# DSO_Power.net
KiCad netlist of a schematic drawn in Altium Designer
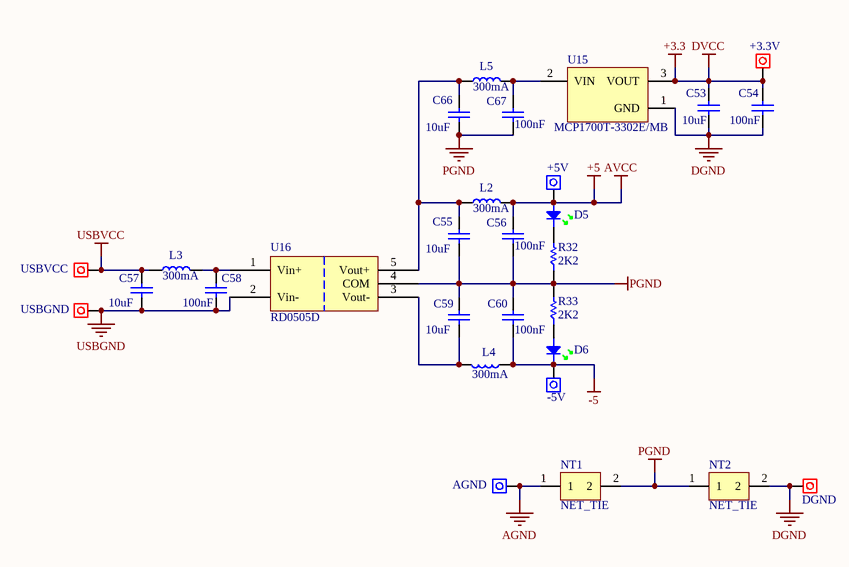
[diagram p0: DSO_Power.SchDoc]

(export (version "E")
  (design (tool "Eeschema 10.0.6"))
  (components
    (comp (ref "C53")
      (value "10uF")
      (footprint "0805C")
      (description "Capacitor")
      (fields (field (name "REVIEWED BY") "RM - 2018/08/05"))
      (libsource (lib "DSO") (part "C"))
    )
    (comp (ref "C54")
      (value "100nF")
      (footprint "0805C")
      (description "Capacitor")
      (fields (field (name "REVIEWED BY") "RM - 2018/08/05"))
      (libsource (lib "DSO") (part "C"))
    )
    (comp (ref "C55")
      (value "10uF")
      (footprint "0805C")
      (description "Capacitor")
      (fields (field (name "REVIEWED BY") "RM - 2018/08/05"))
      (libsource (lib "DSO") (part "C"))
    )
    (comp (ref "C56")
      (value "100nF")
      (footprint "0805C")
      (description "Capacitor")
      (fields (field (name "REVIEWED BY") "RM - 2018/08/05"))
      (libsource (lib "DSO") (part "C"))
    )
    (comp (ref "C57")
      (value "10uF")
      (footprint "0805C")
      (description "Capacitor")
      (fields (field (name "REVIEWED BY") "RM - 2018/08/05"))
      (libsource (lib "DSO") (part "C"))
    )
    (comp (ref "C58")
      (value "100nF")
      (footprint "0805C")
      (description "Capacitor")
      (fields (field (name "REVIEWED BY") "RM - 2018/08/05"))
      (libsource (lib "DSO") (part "C"))
    )
    (comp (ref "C59")
      (value "10uF")
      (footprint "0805C")
      (description "Capacitor")
      (fields (field (name "REVIEWED BY") "RM - 2018/08/05"))
      (libsource (lib "DSO") (part "C"))
    )
    (comp (ref "C60")
      (value "100nF")
      (footprint "0805C")
      (description "Capacitor")
      (fields (field (name "REVIEWED BY") "RM - 2018/08/05"))
      (libsource (lib "DSO") (part "C"))
    )
    (comp (ref "C66")
      (value "10uF")
      (footprint "0805C")
      (description "Capacitor")
      (fields (field (name "REVIEWED BY") "RM - 2018/08/05"))
      (libsource (lib "DSO") (part "C"))
    )
    (comp (ref "C67")
      (value "100nF")
      (footprint "0805C")
      (description "Capacitor")
      (fields (field (name "REVIEWED BY") "RM - 2018/08/05"))
      (libsource (lib "DSO") (part "C"))
    )
    (comp (ref "D5")
      (value "+5V")
      (footprint "0805D-GREEN")
      (description "Light Emitting Diode")
      (fields (field (name "REVIEWED BY") "RM - 2018/08/05"))
      (libsource (lib "DSO") (part "LED GREEN"))
    )
    (comp (ref "D6")
      (value "-5V")
      (footprint "0805D-GREEN")
      (description "Light Emitting Diode")
      (fields (field (name "REVIEWED BY") "RM - 2018/08/05"))
      (libsource (lib "DSO") (part "LED GREEN"))
    )
    (comp (ref "L2")
      (value "300mA")
      (footprint "0805")
      (description "Inductor")
      (fields (field (name "REVIEWED BY") "RM - 2018/08/05"))
      (libsource (lib "DSO") (part "I"))
    )
    (comp (ref "L3")
      (value "300mA")
      (footprint "0805")
      (description "Inductor")
      (fields (field (name "REVIEWED BY") "RM - 2018/08/05"))
      (libsource (lib "DSO") (part "I"))
    )
    (comp (ref "L4")
      (value "300mA")
      (footprint "0805")
      (description "Inductor")
      (fields (field (name "REVIEWED BY") "RM - 2018/08/05"))
      (libsource (lib "DSO") (part "I"))
    )
    (comp (ref "L5")
      (value "300mA")
      (footprint "0805")
      (description "Inductor")
      (fields (field (name "REVIEWED BY") "RM - 2018/08/05"))
      (libsource (lib "DSO") (part "I"))
    )
    (comp (ref "NT1")
      (value "NET_TIE")
      (footprint "NET_TIE")
      (description "Net Tie")
      (libsource (lib "DSO") (part "NET_TIE"))
    )
    (comp (ref "NT2")
      (value "NET_TIE")
      (footprint "NET_TIE")
      (description "Net Tie")
      (libsource (lib "DSO") (part "NET_TIE"))
    )
    (comp (ref "R32")
      (value "2K2")
      (footprint "0805")
      (description "Resistor")
      (fields (field (name "REVIEWED BY") "RM - 2018/08/05"))
      (libsource (lib "DSO") (part "R"))
    )
    (comp (ref "R33")
      (value "2K2")
      (footprint "0805")
      (description "Resistor")
      (fields (field (name "REVIEWED BY") "RM - 2018/08/05"))
      (libsource (lib "DSO") (part "R"))
    )
    (comp (ref "TP4")
      (value "+3.3V")
      (footprint "Testpoin")
      (description "Pad")
      (libsource (lib "DSO") (part "Test Point"))
    )
    (comp (ref "TP5")
      (value "DGND")
      (footprint "Testpoin")
      (description "Pad")
      (libsource (lib "DSO") (part "Test Point"))
    )
    (comp (ref "TP6")
      (value "+5V")
      (footprint "PIN 1.8mm")
      (description "Pad")
      (libsource (lib "DSO") (part "WIRE"))
    )
    (comp (ref "TP8")
      (value "USBVCC")
      (footprint "Testpoin")
      (description "Pad")
      (libsource (lib "DSO") (part "Test Point"))
    )
    (comp (ref "TP9")
      (value "USBGND")
      (footprint "Testpoin")
      (description "Pad")
      (libsource (lib "DSO") (part "Test Point"))
    )
    (comp (ref "TP10")
      (value "-5V")
      (footprint "PIN 1.8mm")
      (description "Pad")
      (libsource (lib "DSO") (part "WIRE"))
    )
    (comp (ref "TP11")
      (value "AGND")
      (footprint "PIN 1.8mm")
      (description "Pad")
      (libsource (lib "DSO") (part "WIRE"))
    )
    (comp (ref "U15")
      (value "MCP1700T-3302E/MB")
      (footprint "SOT89")
      (description "Low Quiescent Current LDO, 3-Pin SOT-89, Extended Temperature, Tape and Reel")
      (fields (field (name "REVIEWED BY") "RM - 2018/08/05"))
      (libsource (lib "DSO") (part "MCP1700T"))
    )
    (comp (ref "U16")
      (value "RD0505D")
      (footprint "SIP_NMG")
      (description "(ADV) DC to DC converter 5V in +-5V out")
      (fields (field (name "REVIEWED BY") "RM - 2018/08/05"))
      (libsource (lib "DSO") (part "RD0505D"))
    )
  )
  (nets
    (net (code "1") (name "+3.3") (class "Default")
      (node (ref "C53") (pin "1") (pinfunction "1_1") (pintype "passive"))
      (node (ref "C54") (pin "1") (pinfunction "1_1") (pintype "passive"))
      (node (ref "TP4") (pin "1") (pintype "passive"))
      (node (ref "U15") (pin "3") (pinfunction "VOUT_3") (pintype "power_in"))
    )
    (net (code "2") (name "+5") (class "Default")
      (node (ref "C56") (pin "1") (pinfunction "1_1") (pintype "passive"))
      (node (ref "D5") (pin "A") (pinfunction "A_A") (pintype "passive"))
      (node (ref "L2") (pin "2") (pinfunction "2_2") (pintype "passive"))
      (node (ref "TP6") (pin "1") (pintype "passive"))
    )
    (net (code "3") (name "-5") (class "Default")
      (node (ref "C60") (pin "1") (pinfunction "1_1") (pintype "passive"))
      (node (ref "D6") (pin "K") (pinfunction "K_K") (pintype "passive"))
      (node (ref "L4") (pin "1") (pinfunction "1_1") (pintype "passive"))
      (node (ref "TP10") (pin "1") (pintype "passive"))
    )
    (net (code "4") (name "AGND") (class "Default")
      (node (ref "NT1") (pin "1") (pinfunction "1_1") (pintype "passive"))
      (node (ref "TP11") (pin "1") (pintype "passive"))
    )
    (net (code "5") (name "DGND") (class "Default")
      (node (ref "C53") (pin "2") (pinfunction "2_2") (pintype "passive"))
      (node (ref "C54") (pin "2") (pinfunction "2_2") (pintype "passive"))
      (node (ref "NT2") (pin "2") (pinfunction "2_2") (pintype "passive"))
      (node (ref "TP5") (pin "1") (pintype "passive"))
      (node (ref "U15") (pin "1") (pinfunction "GND_1") (pintype "power_in"))
    )
    (net (code "6") (name "Net-(D5-PadK)") (class "Default")
      (node (ref "D5") (pin "K") (pinfunction "K_K") (pintype "passive"))
      (node (ref "R32") (pin "2") (pintype "passive"))
    )
    (net (code "7") (name "Net-(D6-PadA)") (class "Default")
      (node (ref "D6") (pin "A") (pinfunction "A_A") (pintype "passive"))
      (node (ref "R33") (pin "1") (pintype "passive"))
    )
    (net (code "8") (name "Net-(U15-VIN)") (class "Default")
      (node (ref "C67") (pin "1") (pinfunction "1_1") (pintype "passive"))
      (node (ref "L5") (pin "2") (pinfunction "2_2") (pintype "passive"))
      (node (ref "U15") (pin "2") (pinfunction "VIN_2") (pintype "power_in"))
    )
    (net (code "9") (name "Net-(U16-Vin+)") (class "Default")
      (node (ref "C58") (pin "1") (pinfunction "1_1") (pintype "passive"))
      (node (ref "L3") (pin "2") (pinfunction "2_2") (pintype "passive"))
      (node (ref "U16") (pin "1") (pinfunction "Vin+_1") (pintype "passive"))
    )
    (net (code "10") (name "Net-(U16-Vout+)") (class "Default")
      (node (ref "C55") (pin "1") (pinfunction "1_1") (pintype "passive"))
      (node (ref "C66") (pin "1") (pinfunction "1_1") (pintype "passive"))
      (node (ref "L2") (pin "1") (pinfunction "1_1") (pintype "passive"))
      (node (ref "L5") (pin "1") (pinfunction "1_1") (pintype "passive"))
      (node (ref "U16") (pin "5") (pinfunction "Vout+_5") (pintype "passive"))
    )
    (net (code "11") (name "Net-(U16-Vout-)") (class "Default")
      (node (ref "C59") (pin "1") (pinfunction "1_1") (pintype "passive"))
      (node (ref "L4") (pin "2") (pinfunction "2_2") (pintype "passive"))
      (node (ref "U16") (pin "3") (pinfunction "Vout-_3") (pintype "passive"))
    )
    (net (code "12") (name "PGND") (class "Default")
      (node (ref "C55") (pin "2") (pinfunction "2_2") (pintype "passive"))
      (node (ref "C56") (pin "2") (pinfunction "2_2") (pintype "passive"))
      (node (ref "C59") (pin "2") (pinfunction "2_2") (pintype "passive"))
      (node (ref "C60") (pin "2") (pinfunction "2_2") (pintype "passive"))
      (node (ref "C66") (pin "2") (pinfunction "2_2") (pintype "passive"))
      (node (ref "C67") (pin "2") (pinfunction "2_2") (pintype "passive"))
      (node (ref "NT1") (pin "2") (pinfunction "2_2") (pintype "passive"))
      (node (ref "NT2") (pin "1") (pinfunction "1_1") (pintype "passive"))
      (node (ref "R32") (pin "1") (pintype "passive"))
      (node (ref "R33") (pin "2") (pintype "passive"))
      (node (ref "U16") (pin "4") (pinfunction "COM_4") (pintype "passive"))
    )
    (net (code "13") (name "USBGND") (class "Default")
      (node (ref "C57") (pin "2") (pinfunction "2_2") (pintype "passive"))
      (node (ref "C58") (pin "2") (pinfunction "2_2") (pintype "passive"))
      (node (ref "TP9") (pin "1") (pintype "passive"))
      (node (ref "U16") (pin "2") (pinfunction "Vin-_2") (pintype "passive"))
    )
    (net (code "14") (name "USBVCC") (class "Default")
      (node (ref "C57") (pin "1") (pinfunction "1_1") (pintype "passive"))
      (node (ref "L3") (pin "1") (pinfunction "1_1") (pintype "passive"))
      (node (ref "TP8") (pin "1") (pintype "passive"))
    )
  )
)
